# p2_regulator.net
KiCad netlist of a schematic drawn in Altium Designer
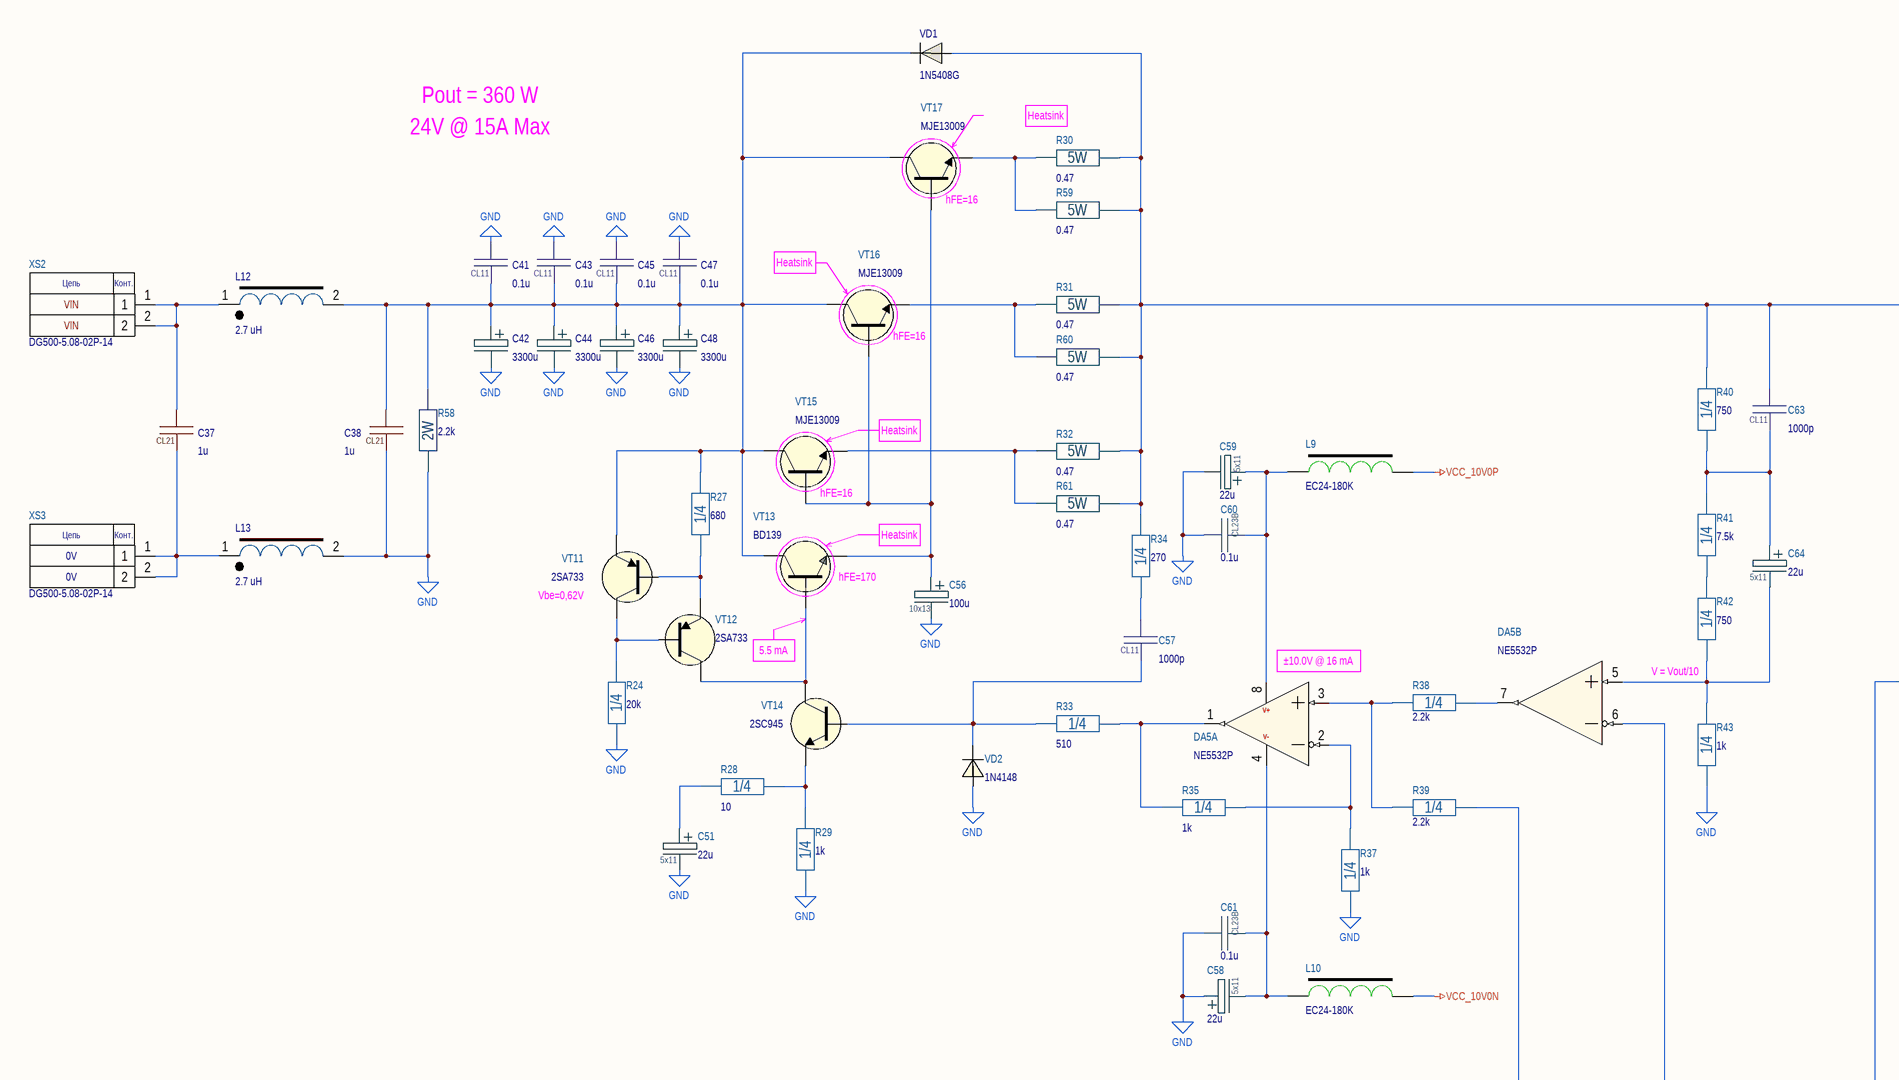
[diagram p0: p2_regulator.SchDoc, top left]
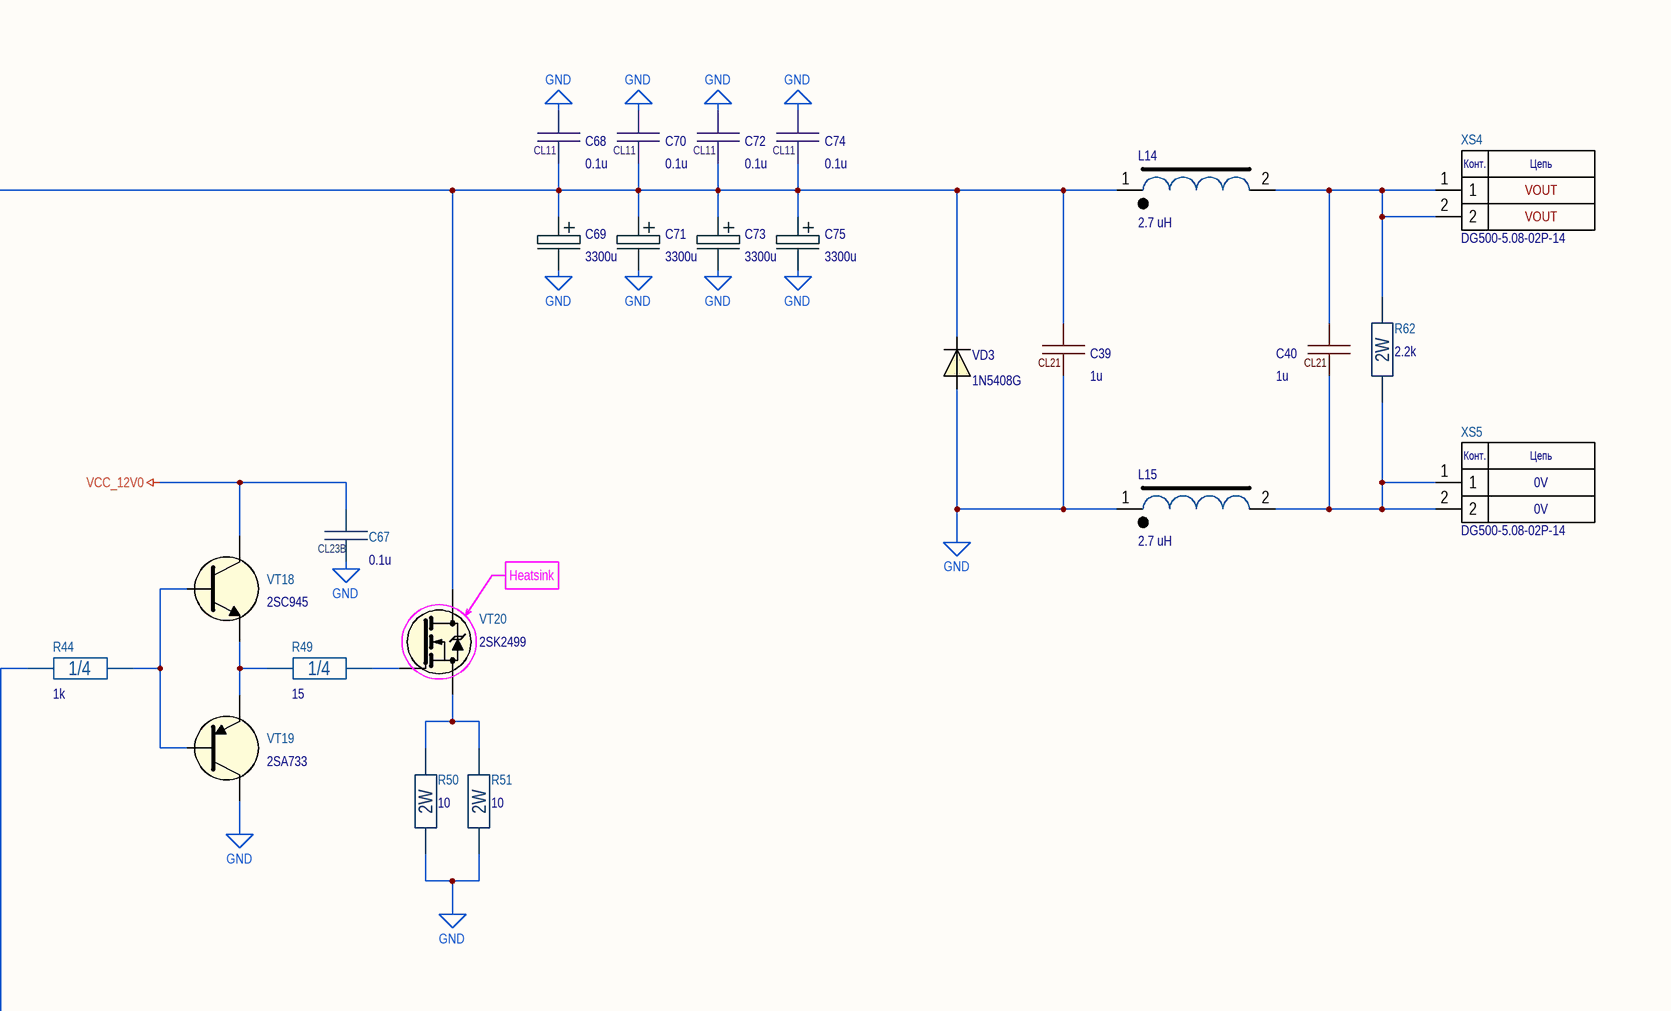
[diagram p1: p2_regulator.SchDoc, top right]
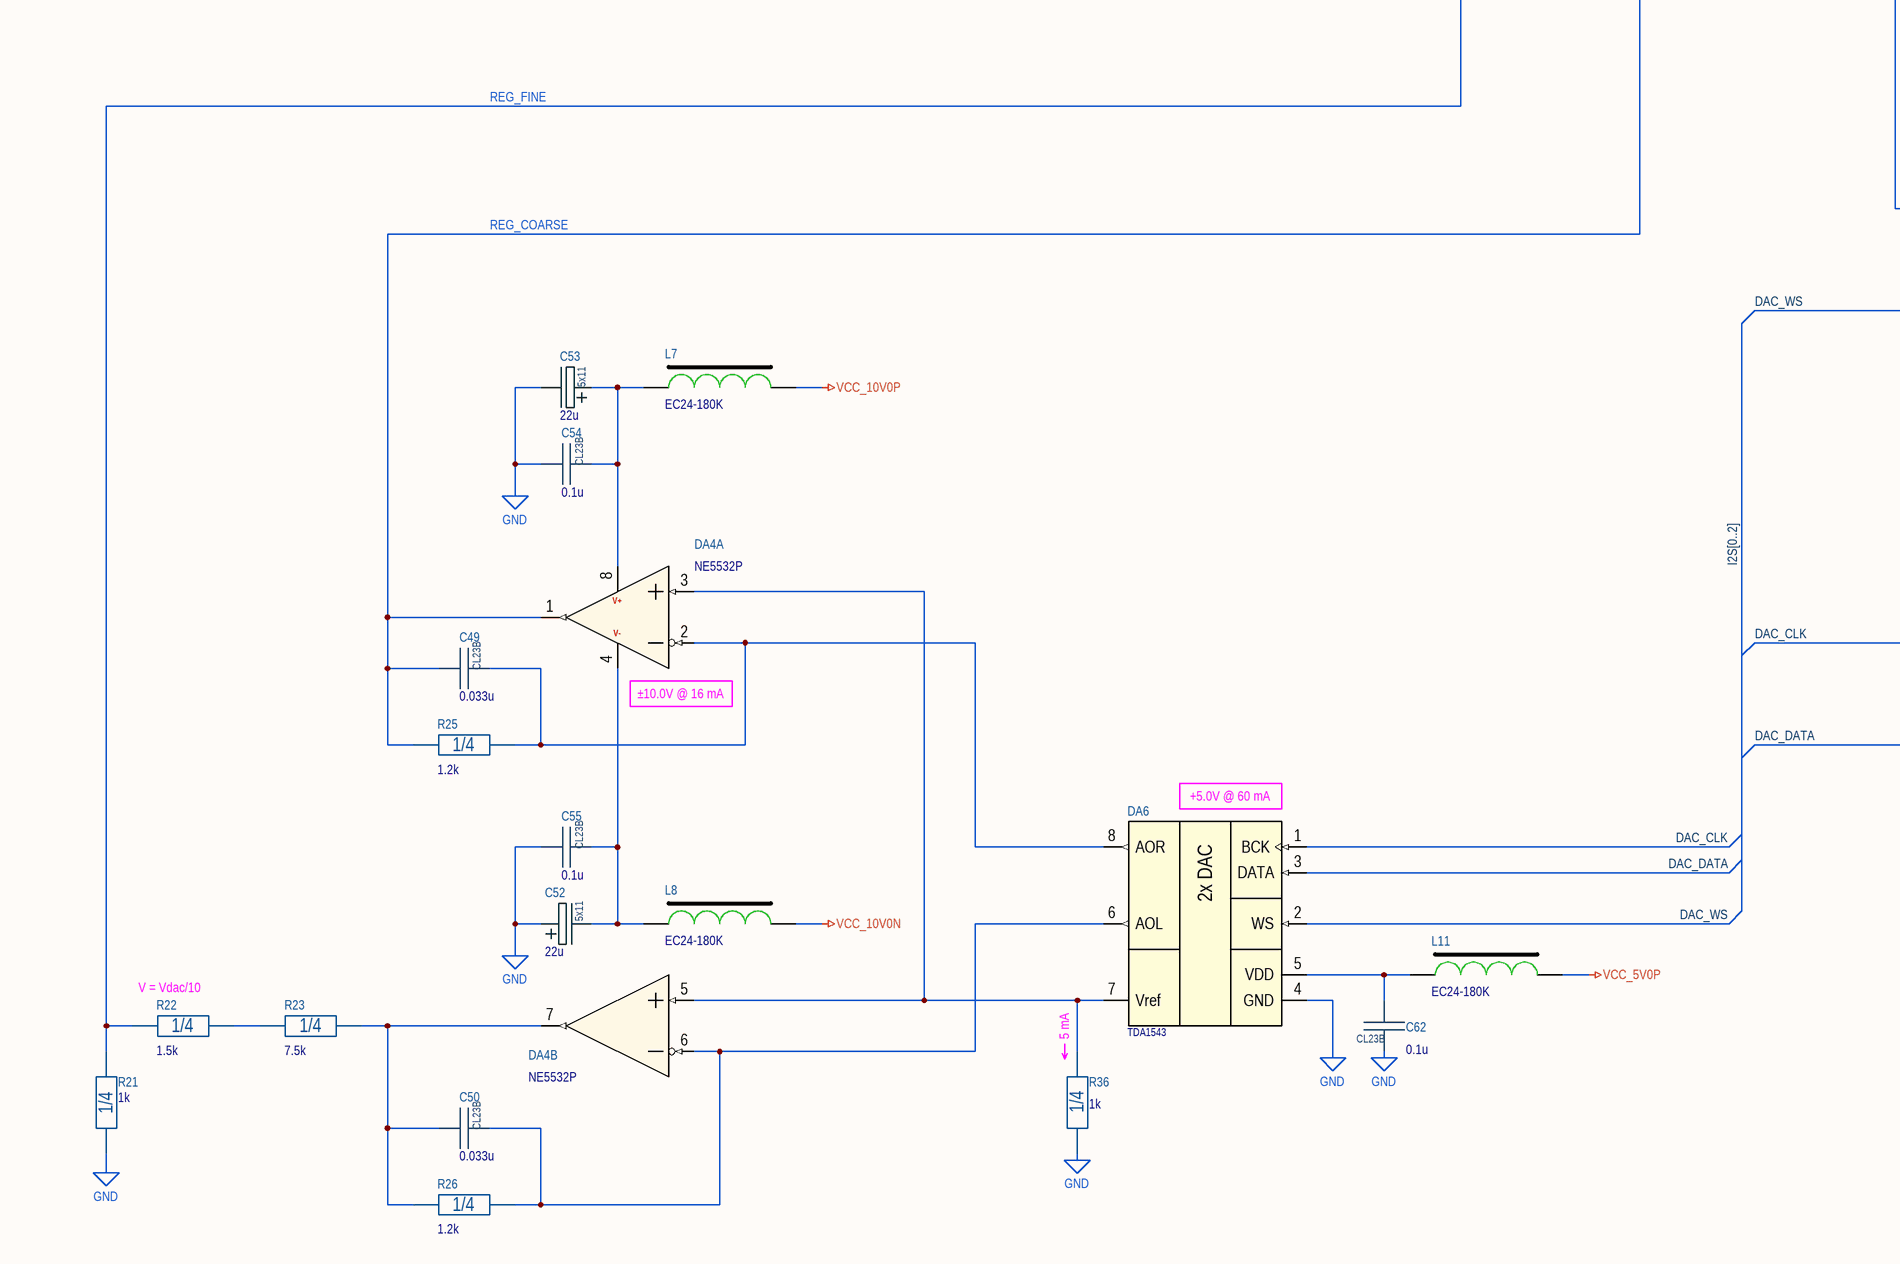
[diagram p2: p2_regulator.SchDoc, bottom left]
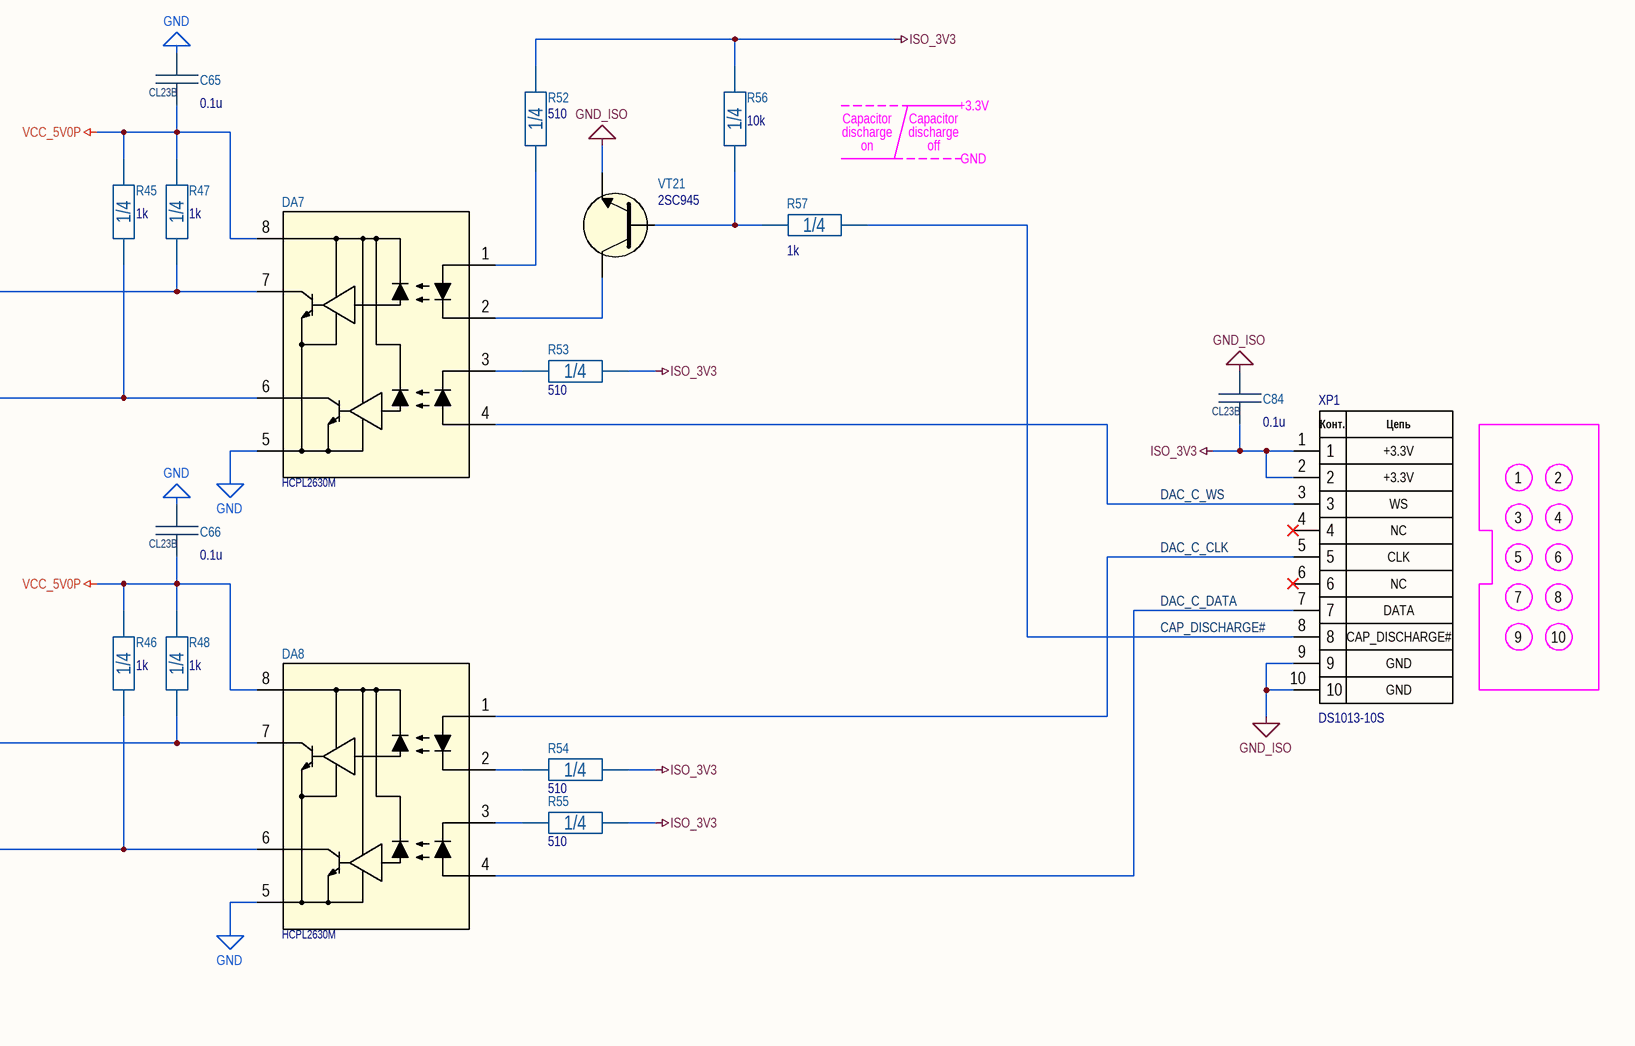
[diagram p3: p2_regulator.SchDoc, bottom right]

(export (version "E")
  (design (tool "Eeschema 10.0.6"))
  (components
    (comp (ref "C37")
      (value "1u")
      (footprint "PcbLib_RC:CL21_29x13.5x6.5_P27.5")
      (description "CL21 Type Metallized Polyester Film Capacitor")
      (fields
        (field (name "TOLERANCE") "± * %")
        (field (name "VOLTAGE") "250V")
        (field (name "PACKAGE") "CL21")
      )
      (libsource (lib "Schlib_RC") (part "CL21"))
    )
    (comp (ref "C38")
      (value "1u")
      (footprint "PcbLib_RC:CL21_29x13.5x6.5_P27.5")
      (description "CL21 Type Metallized Polyester Film Capacitor")
      (fields
        (field (name "TOLERANCE") "± * %")
        (field (name "VOLTAGE") "250V")
        (field (name "PACKAGE") "CL21")
      )
      (libsource (lib "Schlib_RC") (part "CL21"))
    )
    (comp (ref "C39")
      (value "1u")
      (footprint "PcbLib_RC:CL21_29x13.5x6.5_P27.5")
      (description "CL21 Type Metallized Polyester Film Capacitor")
      (fields
        (field (name "TOLERANCE") "± * %")
        (field (name "VOLTAGE") "250V")
        (field (name "PACKAGE") "CL21")
      )
      (libsource (lib "Schlib_RC") (part "CL21"))
    )
    (comp (ref "C40")
      (value "1u")
      (footprint "PcbLib_RC:CL21_29x13.5x6.5_P27.5")
      (description "CL21 Type Metallized Polyester Film Capacitor")
      (fields
        (field (name "TOLERANCE") "± * %")
        (field (name "VOLTAGE") "250V")
        (field (name "PACKAGE") "CL21")
      )
      (libsource (lib "Schlib_RC") (part "CL21"))
    )
    (comp (ref "C41")
      (value "0.1u")
      (footprint "PcbLib_RC:CL11_11.5x7_P7.5")
      (description "CL11 Type Polyester Film Metal Foil Capacitor-inductive")
      (fields
        (field (name "TOLERANCE") "± * %")
        (field (name "VOLTAGE") "100V")
        (field (name "PACKAGE") "CL11")
      )
      (libsource (lib "Schlib_RC") (part "CL11"))
    )
    (comp (ref "C42")
      (value "3300u")
      (footprint "PcbLib_RC:ECAP16X36X75_BLK")
      (description "Aluminium capacitor")
      (fields (field (name "TOLERANCE") "± 20 %") (field (name "VOLTAGE") "50V"))
      (libsource (lib "Schlib_RC") (part "C_ECAP"))
    )
    (comp (ref "C43")
      (value "0.1u")
      (footprint "PcbLib_RC:CL11_11.5x7_P7.5")
      (description "CL11 Type Polyester Film Metal Foil Capacitor-inductive")
      (fields
        (field (name "TOLERANCE") "± * %")
        (field (name "VOLTAGE") "100V")
        (field (name "PACKAGE") "CL11")
      )
      (libsource (lib "Schlib_RC") (part "CL11"))
    )
    (comp (ref "C44")
      (value "3300u")
      (footprint "PcbLib_RC:ECAP16X36X75_BLK")
      (description "Aluminium capacitor")
      (fields (field (name "TOLERANCE") "± 20 %") (field (name "VOLTAGE") "50V"))
      (libsource (lib "Schlib_RC") (part "C_ECAP"))
    )
    (comp (ref "C45")
      (value "0.1u")
      (footprint "PcbLib_RC:CL11_11.5x7_P7.5")
      (description "CL11 Type Polyester Film Metal Foil Capacitor-inductive")
      (fields
        (field (name "TOLERANCE") "± * %")
        (field (name "VOLTAGE") "100V")
        (field (name "PACKAGE") "CL11")
      )
      (libsource (lib "Schlib_RC") (part "CL11"))
    )
    (comp (ref "C46")
      (value "3300u")
      (footprint "PcbLib_RC:ECAP16X36X75_BLK")
      (description "Aluminium capacitor")
      (fields (field (name "TOLERANCE") "± 20 %") (field (name "VOLTAGE") "50V"))
      (libsource (lib "Schlib_RC") (part "C_ECAP"))
    )
    (comp (ref "C47")
      (value "0.1u")
      (footprint "PcbLib_RC:CL11_11.5x7_P7.5")
      (description "CL11 Type Polyester Film Metal Foil Capacitor-inductive")
      (fields
        (field (name "TOLERANCE") "± * %")
        (field (name "VOLTAGE") "100V")
        (field (name "PACKAGE") "CL11")
      )
      (libsource (lib "Schlib_RC") (part "CL11"))
    )
    (comp (ref "C48")
      (value "3300u")
      (footprint "PcbLib_RC:ECAP16X36X75_BLK")
      (description "Aluminium capacitor")
      (fields (field (name "TOLERANCE") "± 20 %") (field (name "VOLTAGE") "50V"))
      (libsource (lib "Schlib_RC") (part "C_ECAP"))
    )
    (comp (ref "C49")
      (value "0.033u")
      (footprint "PcbLib_RC:CL23B_7.2x2.5")
      (description "Box-type metallized polyester film capacitor")
      (fields
        (field (name "TOLERANCE") "± * %")
        (field (name "VOLTAGE") "63V")
        (field (name "PACKAGE") "CL23B")
      )
      (libsource (lib "Schlib_RC") (part "CL23B"))
    )
    (comp (ref "C50")
      (value "0.033u")
      (footprint "PcbLib_RC:CL23B_7.2x2.5")
      (description "Box-type metallized polyester film capacitor")
      (fields
        (field (name "TOLERANCE") "± * %")
        (field (name "VOLTAGE") "63V")
        (field (name "PACKAGE") "CL23B")
      )
      (libsource (lib "Schlib_RC") (part "CL23B"))
    )
    (comp (ref "C51")
      (value "22u")
      (footprint "PcbLib_RC:ECAP5X11X2.0_BRW")
      (description "Aluminium capacitor")
      (fields
        (field (name "TOLERANCE") "± 20 %")
        (field (name "VOLTAGE") "63V")
        (field (name "PACKAGE") "5x11")
      )
      (libsource (lib "Schlib_RC") (part "C_ECAP"))
    )
    (comp (ref "C52")
      (value "22u")
      (footprint "PcbLib_RC:ECAP5X11X2.0_BRW")
      (description "Aluminium capacitor")
      (fields
        (field (name "TOLERANCE") "± 20 %")
        (field (name "VOLTAGE") "63V")
        (field (name "PACKAGE") "5x11")
      )
      (libsource (lib "Schlib_RC") (part "C_ECAP"))
    )
    (comp (ref "C53")
      (value "22u")
      (footprint "PcbLib_RC:ECAP5X11X2.0_BRW")
      (description "Aluminium capacitor")
      (fields
        (field (name "TOLERANCE") "± 20 %")
        (field (name "VOLTAGE") "63V")
        (field (name "PACKAGE") "5x11")
      )
      (libsource (lib "Schlib_RC") (part "C_ECAP"))
    )
    (comp (ref "C54")
      (value "0.1u")
      (footprint "PcbLib_RC:CL23B_7.2x2.5")
      (description "Box-type metallized polyester film capacitor")
      (fields
        (field (name "TOLERANCE") "± * %")
        (field (name "VOLTAGE") "63V")
        (field (name "PACKAGE") "CL23B")
      )
      (libsource (lib "Schlib_RC") (part "CL23B"))
    )
    (comp (ref "C55")
      (value "0.1u")
      (footprint "PcbLib_RC:CL23B_7.2x2.5")
      (description "Box-type metallized polyester film capacitor")
      (fields
        (field (name "TOLERANCE") "± * %")
        (field (name "VOLTAGE") "63V")
        (field (name "PACKAGE") "CL23B")
      )
      (libsource (lib "Schlib_RC") (part "CL23B"))
    )
    (comp (ref "C56")
      (value "100u")
      (footprint "PcbLib_RC:ECAP10X13X5_BRW")
      (description "Aluminium capacitor")
      (fields
        (field (name "TOLERANCE") "± 20 %")
        (field (name "VOLTAGE") "63V")
        (field (name "PACKAGE") "10x13")
      )
      (libsource (lib "Schlib_RC") (part "C_ECAP"))
    )
    (comp (ref "C57")
      (value "1000p")
      (footprint "PcbLib_RC:CL11_6x3.5_P3.5")
      (description "CL11 Type Polyester Film Metal Foil Capacitor-inductive")
      (fields
        (field (name "TOLERANCE") "± 5 %")
        (field (name "VOLTAGE") "100V")
        (field (name "PACKAGE") "CL11")
      )
      (libsource (lib "Schlib_RC") (part "CL11"))
    )
    (comp (ref "C58")
      (value "22u")
      (footprint "PcbLib_RC:ECAP5X11X2.0_BRW")
      (description "Aluminium capacitor")
      (fields
        (field (name "TOLERANCE") "± 20 %")
        (field (name "VOLTAGE") "63V")
        (field (name "PACKAGE") "5x11")
      )
      (libsource (lib "Schlib_RC") (part "C_ECAP"))
    )
    (comp (ref "C59")
      (value "22u")
      (footprint "PcbLib_RC:ECAP5X11X2.0_BRW")
      (description "Aluminium capacitor")
      (fields
        (field (name "TOLERANCE") "± 20 %")
        (field (name "VOLTAGE") "63V")
        (field (name "PACKAGE") "5x11")
      )
      (libsource (lib "Schlib_RC") (part "C_ECAP"))
    )
    (comp (ref "C60")
      (value "0.1u")
      (footprint "PcbLib_RC:CL23B_7.2x2.5")
      (description "Box-type metallized polyester film capacitor")
      (fields
        (field (name "TOLERANCE") "± * %")
        (field (name "VOLTAGE") "63V")
        (field (name "PACKAGE") "CL23B")
      )
      (libsource (lib "Schlib_RC") (part "CL23B"))
    )
    (comp (ref "C61")
      (value "0.1u")
      (footprint "PcbLib_RC:CL23B_7.2x2.5")
      (description "Box-type metallized polyester film capacitor")
      (fields
        (field (name "TOLERANCE") "± * %")
        (field (name "VOLTAGE") "63V")
        (field (name "PACKAGE") "CL23B")
      )
      (libsource (lib "Schlib_RC") (part "CL23B"))
    )
    (comp (ref "C62")
      (value "0.1u")
      (footprint "PcbLib_RC:CL23B_7.2x2.5")
      (description "Box-type metallized polyester film capacitor")
      (fields
        (field (name "TOLERANCE") "± * %")
        (field (name "VOLTAGE") "63V")
        (field (name "PACKAGE") "CL23B")
      )
      (libsource (lib "Schlib_RC") (part "CL23B"))
    )
    (comp (ref "C63")
      (value "1000p")
      (footprint "PcbLib_RC:CL11_6x3.5_P3.5")
      (description "CL11 Type Polyester Film Metal Foil Capacitor-inductive")
      (fields
        (field (name "TOLERANCE") "± 5 %")
        (field (name "VOLTAGE") "100V")
        (field (name "PACKAGE") "CL11")
      )
      (libsource (lib "Schlib_RC") (part "CL11"))
    )
    (comp (ref "C64")
      (value "22u")
      (footprint "PcbLib_RC:ECAP5X11X2.0_BRW")
      (description "Aluminium capacitor")
      (fields
        (field (name "TOLERANCE") "± 20 %")
        (field (name "VOLTAGE") "63V")
        (field (name "PACKAGE") "5x11")
      )
      (libsource (lib "Schlib_RC") (part "C_ECAP"))
    )
    (comp (ref "C65")
      (value "0.1u")
      (footprint "PcbLib_RC:CL23B_7.2x2.5")
      (description "Box-type metallized polyester film capacitor")
      (fields
        (field (name "TOLERANCE") "± * %")
        (field (name "VOLTAGE") "63V")
        (field (name "PACKAGE") "CL23B")
      )
      (libsource (lib "Schlib_RC") (part "CL23B"))
    )
    (comp (ref "C66")
      (value "0.1u")
      (footprint "PcbLib_RC:CL23B_7.2x2.5")
      (description "Box-type metallized polyester film capacitor")
      (fields
        (field (name "TOLERANCE") "± * %")
        (field (name "VOLTAGE") "63V")
        (field (name "PACKAGE") "CL23B")
      )
      (libsource (lib "Schlib_RC") (part "CL23B"))
    )
    (comp (ref "C67")
      (value "0.1u")
      (footprint "PcbLib_RC:CL23B_7.2x2.5")
      (description "Box-type metallized polyester film capacitor")
      (fields
        (field (name "TOLERANCE") "± * %")
        (field (name "VOLTAGE") "63V")
        (field (name "PACKAGE") "CL23B")
      )
      (libsource (lib "Schlib_RC") (part "CL23B"))
    )
    (comp (ref "C68")
      (value "0.1u")
      (footprint "PcbLib_RC:CL11_11.5x7_P7.5")
      (description "CL11 Type Polyester Film Metal Foil Capacitor-inductive")
      (fields
        (field (name "TOLERANCE") "± * %")
        (field (name "VOLTAGE") "100V")
        (field (name "PACKAGE") "CL11")
      )
      (libsource (lib "Schlib_RC") (part "CL11"))
    )
    (comp (ref "C69")
      (value "3300u")
      (footprint "PcbLib_RC:ECAP16X36X75_BLK")
      (description "Aluminium capacitor")
      (fields (field (name "TOLERANCE") "± 20 %") (field (name "VOLTAGE") "50V"))
      (libsource (lib "Schlib_RC") (part "C_ECAP"))
    )
    (comp (ref "C70")
      (value "0.1u")
      (footprint "PcbLib_RC:CL11_11.5x7_P7.5")
      (description "CL11 Type Polyester Film Metal Foil Capacitor-inductive")
      (fields
        (field (name "TOLERANCE") "± * %")
        (field (name "VOLTAGE") "100V")
        (field (name "PACKAGE") "CL11")
      )
      (libsource (lib "Schlib_RC") (part "CL11"))
    )
    (comp (ref "C71")
      (value "3300u")
      (footprint "PcbLib_RC:ECAP16X36X75_BLK")
      (description "Aluminium capacitor")
      (fields (field (name "TOLERANCE") "± 20 %") (field (name "VOLTAGE") "50V"))
      (libsource (lib "Schlib_RC") (part "C_ECAP"))
    )
    (comp (ref "C72")
      (value "0.1u")
      (footprint "PcbLib_RC:CL11_11.5x7_P7.5")
      (description "CL11 Type Polyester Film Metal Foil Capacitor-inductive")
      (fields
        (field (name "TOLERANCE") "± * %")
        (field (name "VOLTAGE") "100V")
        (field (name "PACKAGE") "CL11")
      )
      (libsource (lib "Schlib_RC") (part "CL11"))
    )
    (comp (ref "C73")
      (value "3300u")
      (footprint "PcbLib_RC:ECAP16X36X75_BLK")
      (description "Aluminium capacitor")
      (fields (field (name "TOLERANCE") "± 20 %") (field (name "VOLTAGE") "50V"))
      (libsource (lib "Schlib_RC") (part "C_ECAP"))
    )
    (comp (ref "C74")
      (value "0.1u")
      (footprint "PcbLib_RC:CL11_11.5x7_P7.5")
      (description "CL11 Type Polyester Film Metal Foil Capacitor-inductive")
      (fields
        (field (name "TOLERANCE") "± * %")
        (field (name "VOLTAGE") "100V")
        (field (name "PACKAGE") "CL11")
      )
      (libsource (lib "Schlib_RC") (part "CL11"))
    )
    (comp (ref "C75")
      (value "3300u")
      (footprint "PcbLib_RC:ECAP16X36X75_BLK")
      (description "Aluminium capacitor")
      (fields (field (name "TOLERANCE") "± 20 %") (field (name "VOLTAGE") "50V"))
      (libsource (lib "Schlib_RC") (part "C_ECAP"))
    )
    (comp (ref "C84")
      (value "0.1u")
      (footprint "PcbLib_RC:CL23B_7.2x2.5")
      (description "Box-type metallized polyester film capacitor")
      (fields
        (field (name "TOLERANCE") "± * %")
        (field (name "VOLTAGE") "63V")
        (field (name "PACKAGE") "CL23B")
      )
      (libsource (lib "Schlib_RC") (part "CL23B"))
    )
    (comp (ref "DA4")
      (value "NE5532P")
      (footprint "PcbLib_ICs:DIP-8P-M01_with_SO8")
      (description "DUAL LOW-NOISE OPERATIONAL AMPLIFIERS")
      (fields (field (name "MANUFACTURER") "Texas Instruments"))
      (libsource (lib "Schlib_Texas_Instruments") (part "NE5532P"))
    )
    (comp (ref "DA5")
      (value "NE5532P")
      (footprint "PcbLib_ICs:DIP-8P-M01")
      (description "DUAL LOW-NOISE OPERATIONAL AMPLIFIERS")
      (fields (field (name "MANUFACTURER") "Texas Instruments"))
      (libsource (lib "Schlib_Texas_Instruments") (part "NE5532P"))
    )
    (comp (ref "DA6")
      (value "TDA1543")
      (footprint "PcbLib_ICs:DIP-8P-M01")
      (description "Dual 16-bit DAC, I2S input format")
      (fields (field (name "MANUFACTURER") "Philips"))
      (libsource (lib "Schlib_OtherComponents") (part "TDA1543"))
    )
    (comp (ref "DA7")
      (value "HCPL2630M")
      (footprint "PcbLib_ICs:DIP-8P-M01")
      (description "Dual-Channel High-Speed 10 MBit/s Logic Gate Optocouplers")
      (fields (field (name "MANUFACTURER") "ON Semiconductor"))
      (libsource (lib "Schlib_ONSemiconductor") (part "HCPL2630M"))
    )
    (comp (ref "DA8")
      (value "HCPL2630M")
      (footprint "PcbLib_ICs:DIP-8P-M01")
      (description "Dual-Channel High-Speed 10 MBit/s Logic Gate Optocouplers")
      (fields (field (name "MANUFACTURER") "ON Semiconductor"))
      (libsource (lib "Schlib_ONSemiconductor") (part "HCPL2630M"))
    )
    (comp (ref "L7")
      (value "EC24-180K")
      (footprint "PcbLib_RC:EC24_GREEN")
      (description "Axial leaded coated inductors")
      (fields (field (name "MANUFACTURER") "3L Electronic"))
      (libsource (lib "Schlib_RC") (part "EC24"))
    )
    (comp (ref "L8")
      (value "EC24-180K")
      (footprint "PcbLib_RC:EC24_GREEN")
      (description "Axial leaded coated inductors")
      (fields (field (name "MANUFACTURER") "3L Electronic"))
      (libsource (lib "Schlib_RC") (part "EC24"))
    )
    (comp (ref "L9")
      (value "EC24-180K")
      (footprint "PcbLib_RC:EC24_GREEN")
      (description "Axial leaded coated inductors")
      (fields (field (name "MANUFACTURER") "3L Electronic"))
      (libsource (lib "Schlib_RC") (part "EC24"))
    )
    (comp (ref "L10")
      (value "EC24-180K")
      (footprint "PcbLib_RC:EC24_GREEN")
      (description "Axial leaded coated inductors")
      (fields (field (name "MANUFACTURER") "3L Electronic"))
      (libsource (lib "Schlib_RC") (part "EC24"))
    )
    (comp (ref "L11")
      (value "EC24-180K")
      (footprint "PcbLib_RC:EC24_GREEN")
      (description "Axial leaded coated inductors")
      (fields (field (name "MANUFACTURER") "3L Electronic"))
      (libsource (lib "Schlib_RC") (part "EC24"))
    )
    (comp (ref "L12")
      (value "2.7 uH")
      (footprint "PcbLib_RC:CORE_D20_GB")
      (description "Ferrite Core D20.3/12.7/6.35 mm")
      (libsource (lib "Schlib_OtherComponents") (part "CORE_D20"))
    )
    (comp (ref "L13")
      (value "2.7 uH")
      (footprint "PcbLib_RC:CORE_D20_GB")
      (description "Ferrite Core D20.3/12.7/6.35 mm")
      (libsource (lib "Schlib_OtherComponents") (part "CORE_D20"))
    )
    (comp (ref "L14")
      (value "2.7 uH")
      (footprint "PcbLib_RC:CORE_D20_GB")
      (description "Ferrite Core D20.3/12.7/6.35 mm")
      (libsource (lib "Schlib_OtherComponents") (part "CORE_D20"))
    )
    (comp (ref "L15")
      (value "2.7 uH")
      (footprint "PcbLib_RC:CORE_D20_GB")
      (description "Ferrite Core D20.3/12.7/6.35 mm")
      (libsource (lib "Schlib_OtherComponents") (part "CORE_D20"))
    )
    (comp (ref "R21")
      (value "1k")
      (footprint "PcbLib_RC:CFR-25")
      (description "Resistor 1/4W")
      (fields
        (field (name "TOLERANCE") "± 1 %")
        (field (name "PART NUMBER") "MFR-25FTF52-10K")
        (field (name "PACKAGE") "1/4")
      )
      (libsource (lib "Schlib_RC") (part "CF25"))
    )
    (comp (ref "R22")
      (value "1.5k")
      (footprint "PcbLib_RC:CFR-25")
      (description "Resistor 1/4W")
      (fields
        (field (name "TOLERANCE") "± 1 %")
        (field (name "PART NUMBER") "MFR-25FTF52-1K5")
        (field (name "PACKAGE") "1/4")
      )
      (libsource (lib "Schlib_RC") (part "CF25"))
    )
    (comp (ref "R23")
      (value "7.5k")
      (footprint "PcbLib_RC:CFR-25")
      (description "Resistor 1/4W")
      (fields
        (field (name "TOLERANCE") "± 1 %")
        (field (name "PART NUMBER") "MFR-25FTF52-7K5")
        (field (name "PACKAGE") "1/4")
      )
      (libsource (lib "Schlib_RC") (part "CF25"))
    )
    (comp (ref "R24")
      (value "20k")
      (footprint "PcbLib_RC:CFR-25")
      (description "Resistor 1/4W")
      (fields
        (field (name "TOLERANCE") "± 1 %")
        (field (name "PART NUMBER") "MFR-25FTF52-20K")
        (field (name "PACKAGE") "1/4")
      )
      (libsource (lib "Schlib_RC") (part "CF25"))
    )
    (comp (ref "R25")
      (value "1.2k")
      (footprint "PcbLib_RC:CFR-25")
      (description "Resistor 1/4W")
      (fields
        (field (name "TOLERANCE") "± 1 %")
        (field (name "PART NUMBER") "MFR-25FTF52-1K2")
        (field (name "PACKAGE") "1/4")
      )
      (libsource (lib "Schlib_RC") (part "CF25"))
    )
    (comp (ref "R26")
      (value "1.2k")
      (footprint "PcbLib_RC:CFR-25")
      (description "Resistor 1/4W")
      (fields
        (field (name "TOLERANCE") "± 1 %")
        (field (name "PART NUMBER") "MFR-25FTF52-1K2")
        (field (name "PACKAGE") "1/4")
      )
      (libsource (lib "Schlib_RC") (part "CF25"))
    )
    (comp (ref "R27")
      (value "680")
      (footprint "PcbLib_RC:CFR-25")
      (description "Resistor 1/4W")
      (fields
        (field (name "TOLERANCE") "± 1 %")
        (field (name "PART NUMBER") "MFR-25FTF52-680R")
        (field (name "PACKAGE") "1/4")
      )
      (libsource (lib "Schlib_RC") (part "CF25"))
    )
    (comp (ref "R28")
      (value "10")
      (footprint "PcbLib_RC:CFR-25")
      (description "Resistor 1/4W")
      (fields
        (field (name "TOLERANCE") "± 1 %")
        (field (name "PART NUMBER") "MFR-25FTF52-10R")
        (field (name "PACKAGE") "1/4")
      )
      (libsource (lib "Schlib_RC") (part "CF25"))
    )
    (comp (ref "R29")
      (value "1k")
      (footprint "PcbLib_RC:CFR-25")
      (description "Resistor 1/4W")
      (fields
        (field (name "TOLERANCE") "± 1 %")
        (field (name "PART NUMBER") "MFR-25FTF52-10K")
        (field (name "PACKAGE") "1/4")
      )
      (libsource (lib "Schlib_RC") (part "CF25"))
    )
    (comp (ref "R30")
      (value "0.47")
      (footprint "PcbLib_RC:BPR58")
      (description "Rectangular type metal plate resistors")
      (fields
        (field (name "TOLERANCE") "± 5 %")
        (field (name "PART NUMBER") "BPR58CR47J")
        (field (name "PACKAGE") "5W")
      )
      (libsource (lib "Schlib_RC") (part "BPR58"))
    )
    (comp (ref "R31")
      (value "0.47")
      (footprint "PcbLib_RC:BPR58")
      (description "Rectangular type metal plate resistors")
      (fields
        (field (name "TOLERANCE") "± 5 %")
        (field (name "PART NUMBER") "BPR58CR47J")
        (field (name "PACKAGE") "5W")
      )
      (libsource (lib "Schlib_RC") (part "BPR58"))
    )
    (comp (ref "R32")
      (value "0.47")
      (footprint "PcbLib_RC:BPR58")
      (description "Rectangular type metal plate resistors")
      (fields
        (field (name "TOLERANCE") "± 5 %")
        (field (name "PART NUMBER") "BPR58CR47J")
        (field (name "PACKAGE") "5W")
      )
      (libsource (lib "Schlib_RC") (part "BPR58"))
    )
    (comp (ref "R33")
      (value "510")
      (footprint "PcbLib_RC:CFR-25")
      (description "Resistor 1/4W")
      (fields
        (field (name "TOLERANCE") "± 1 %")
        (field (name "PART NUMBER") "MFR-25FTF52-510R")
        (field (name "PACKAGE") "1/4")
      )
      (libsource (lib "Schlib_RC") (part "CF25"))
    )
    (comp (ref "R34")
      (value "270")
      (footprint "PcbLib_RC:CFR-25")
      (description "Resistor 1/4W")
      (fields
        (field (name "TOLERANCE") "± 1 %")
        (field (name "PART NUMBER") "MFR-25FTF52-270R")
        (field (name "PACKAGE") "1/4")
      )
      (libsource (lib "Schlib_RC") (part "CF25"))
    )
    (comp (ref "R35")
      (value "1k")
      (footprint "PcbLib_RC:CFR-25")
      (description "Resistor 1/4W")
      (fields
        (field (name "TOLERANCE") "± 1 %")
        (field (name "PART NUMBER") "MFR-25FTF52-10K")
        (field (name "PACKAGE") "1/4")
      )
      (libsource (lib "Schlib_RC") (part "CF25"))
    )
    (comp (ref "R36")
      (value "1k")
      (footprint "PcbLib_RC:CFR-25")
      (description "Resistor 1/4W")
      (fields
        (field (name "TOLERANCE") "± 0.1 %")
        (field (name "PART NUMBER") "MFP-25BRD52-1K")
        (field (name "PACKAGE") "1/4")
      )
      (libsource (lib "Schlib_RC") (part "CF25"))
    )
    (comp (ref "R37")
      (value "1k")
      (footprint "PcbLib_RC:CFR-25")
      (description "Resistor 1/4W")
      (fields
        (field (name "TOLERANCE") "± 1 %")
        (field (name "PART NUMBER") "MFR-25FTF52-10K")
        (field (name "PACKAGE") "1/4")
      )
      (libsource (lib "Schlib_RC") (part "CF25"))
    )
    (comp (ref "R38")
      (value "2.2k")
      (footprint "PcbLib_RC:CFR-25")
      (description "Resistor 1/4W")
      (fields
        (field (name "TOLERANCE") "± 1 %")
        (field (name "PART NUMBER") "MFR-25FTF52-2K2")
        (field (name "PACKAGE") "1/4")
      )
      (libsource (lib "Schlib_RC") (part "CF25"))
    )
    (comp (ref "R39")
      (value "2.2k")
      (footprint "PcbLib_RC:CFR-25")
      (description "Resistor 1/4W")
      (fields
        (field (name "TOLERANCE") "± 1 %")
        (field (name "PART NUMBER") "MFR-25FTF52-2K2")
        (field (name "PACKAGE") "1/4")
      )
      (libsource (lib "Schlib_RC") (part "CF25"))
    )
    (comp (ref "R40")
      (value "750")
      (footprint "PcbLib_RC:CFR-25")
      (description "Resistor 1/4W")
      (fields
        (field (name "TOLERANCE") "± 1 %")
        (field (name "PART NUMBER") "MFR-25FTF52-750R")
        (field (name "PACKAGE") "1/4")
      )
      (libsource (lib "Schlib_RC") (part "CF25"))
    )
    (comp (ref "R41")
      (value "7.5k")
      (footprint "PcbLib_RC:CFR-25")
      (description "Resistor 1/4W")
      (fields
        (field (name "TOLERANCE") "± 1 %")
        (field (name "PART NUMBER") "MFR-25FTF52-7K5")
        (field (name "PACKAGE") "1/4")
      )
      (libsource (lib "Schlib_RC") (part "CF25"))
    )
    (comp (ref "R42")
      (value "750")
      (footprint "PcbLib_RC:CFR-25")
      (description "Resistor 1/4W")
      (fields
        (field (name "TOLERANCE") "± 1 %")
        (field (name "PART NUMBER") "MFR-25FTF52-750R")
        (field (name "PACKAGE") "1/4")
      )
      (libsource (lib "Schlib_RC") (part "CF25"))
    )
    (comp (ref "R43")
      (value "1k")
      (footprint "PcbLib_RC:CFR-25")
      (description "Resistor 1/4W")
      (fields
        (field (name "TOLERANCE") "± 1 %")
        (field (name "PART NUMBER") "MFR-25FTF52-1K")
        (field (name "PACKAGE") "1/4")
      )
      (libsource (lib "Schlib_RC") (part "CF25"))
    )
    (comp (ref "R44")
      (value "1k")
      (footprint "PcbLib_RC:CFR-25")
      (description "Resistor 1/4W")
      (fields
        (field (name "TOLERANCE") "± 1 %")
        (field (name "PART NUMBER") "MFR-25FTF52-1K")
        (field (name "PACKAGE") "1/4")
      )
      (libsource (lib "Schlib_RC") (part "CF25"))
    )
    (comp (ref "R45")
      (value "1k")
      (footprint "PcbLib_RC:CFR-25")
      (description "Resistor 1/4W")
      (fields
        (field (name "TOLERANCE") "± 1 %")
        (field (name "PART NUMBER") "MFR-25FTF52-1K")
        (field (name "PACKAGE") "1/4")
      )
      (libsource (lib "Schlib_RC") (part "CF25"))
    )
    (comp (ref "R46")
      (value "1k")
      (footprint "PcbLib_RC:CFR-25")
      (description "Resistor 1/4W")
      (fields
        (field (name "TOLERANCE") "± 1 %")
        (field (name "PART NUMBER") "MFR-25FTF52-1K")
        (field (name "PACKAGE") "1/4")
      )
      (libsource (lib "Schlib_RC") (part "CF25"))
    )
    (comp (ref "R47")
      (value "1k")
      (footprint "PcbLib_RC:CFR-25")
      (description "Resistor 1/4W")
      (fields
        (field (name "TOLERANCE") "± 1 %")
        (field (name "PART NUMBER") "MFR-25FTF52-1K")
        (field (name "PACKAGE") "1/4")
      )
      (libsource (lib "Schlib_RC") (part "CF25"))
    )
    (comp (ref "R48")
      (value "1k")
      (footprint "PcbLib_RC:CFR-25")
      (description "Resistor 1/4W")
      (fields
        (field (name "TOLERANCE") "± 1 %")
        (field (name "PART NUMBER") "MFR-25FTF52-1K")
        (field (name "PACKAGE") "1/4")
      )
      (libsource (lib "Schlib_RC") (part "CF25"))
    )
    (comp (ref "R49")
      (value "15")
      (footprint "PcbLib_RC:CFR-25")
      (description "Resistor 1/4W")
      (fields
        (field (name "TOLERANCE") "± 1 %")
        (field (name "PART NUMBER") "MFR-25FTF52-15R")
        (field (name "PACKAGE") "1/4")
      )
      (libsource (lib "Schlib_RC") (part "CF25"))
    )
    (comp (ref "R50")
      (value "10")
      (footprint "PcbLib_RC:CFR-200")
      (description "Resistor 2W")
      (fields
        (field (name "TOLERANCE") "± 5 %")
        (field (name "PART NUMBER") "KNP200JB-73-10R")
        (field (name "PACKAGE") "2W")
      )
      (libsource (lib "Schlib_RC") (part "CF200"))
    )
    (comp (ref "R51")
      (value "10")
      (footprint "PcbLib_RC:CFR-200")
      (description "Resistor 2W")
      (fields
        (field (name "TOLERANCE") "± 5 %")
        (field (name "PART NUMBER") "KNP200JB-73-10R")
        (field (name "PACKAGE") "2W")
      )
      (libsource (lib "Schlib_RC") (part "CF200"))
    )
    (comp (ref "R52")
      (value "510")
      (footprint "PcbLib_RC:CFR-25")
      (description "Resistor 1/4W")
      (fields
        (field (name "TOLERANCE") "± 1 %")
        (field (name "PART NUMBER") "MFR-25FTF52-510R")
        (field (name "PACKAGE") "1/4")
      )
      (libsource (lib "Schlib_RC") (part "CF25"))
    )
    (comp (ref "R53")
      (value "510")
      (footprint "PcbLib_RC:CFR-25")
      (description "Resistor 1/4W")
      (fields
        (field (name "TOLERANCE") "± 1 %")
        (field (name "PART NUMBER") "MFR-25FTF52-510R")
        (field (name "PACKAGE") "1/4")
      )
      (libsource (lib "Schlib_RC") (part "CF25"))
    )
    (comp (ref "R54")
      (value "510")
      (footprint "PcbLib_RC:CFR-25")
      (description "Resistor 1/4W")
      (fields
        (field (name "TOLERANCE") "± 1 %")
        (field (name "PART NUMBER") "MFR-25FTF52-510R")
        (field (name "PACKAGE") "1/4")
      )
      (libsource (lib "Schlib_RC") (part "CF25"))
    )
    (comp (ref "R55")
      (value "510")
      (footprint "PcbLib_RC:CFR-25")
      (description "Resistor 1/4W")
      (fields
        (field (name "TOLERANCE") "± 1 %")
        (field (name "PART NUMBER") "MFR-25FTF52-510R")
        (field (name "PACKAGE") "1/4")
      )
      (libsource (lib "Schlib_RC") (part "CF25"))
    )
    (comp (ref "R56")
      (value "10k")
      (footprint "PcbLib_RC:CFR-25")
      (description "Resistor 1/4W")
      (fields
        (field (name "TOLERANCE") "± 1 %")
        (field (name "PART NUMBER") "MFR-25FTF52-10K")
        (field (name "PACKAGE") "1/4")
      )
      (libsource (lib "Schlib_RC") (part "CF25"))
    )
    (comp (ref "R57")
      (value "1k")
      (footprint "PcbLib_RC:CFR-25")
      (description "Resistor 1/4W")
      (fields
        (field (name "TOLERANCE") "± 1 %")
        (field (name "PART NUMBER") "MFR-25FTF52-1K")
        (field (name "PACKAGE") "1/4")
      )
      (libsource (lib "Schlib_RC") (part "CF25"))
    )
    (comp (ref "R58")
      (value "2.2k")
      (footprint "PcbLib_RC:CFR-200")
      (description "Resistor 2W")
      (fields
        (field (name "TOLERANCE") "± 5 %")
        (field (name "PART NUMBER") "KNP200JB-73-2K2")
        (field (name "PACKAGE") "2W")
      )
      (libsource (lib "Schlib_RC") (part "CF200"))
    )
    (comp (ref "R59")
      (value "0.47")
      (footprint "PcbLib_RC:BPR58")
      (description "Rectangular type metal plate resistors")
      (fields
        (field (name "TOLERANCE") "± 5 %")
        (field (name "PART NUMBER") "BPR58CR47J")
        (field (name "PACKAGE") "5W")
      )
      (libsource (lib "Schlib_RC") (part "BPR58"))
    )
    (comp (ref "R60")
      (value "0.47")
      (footprint "PcbLib_RC:BPR58")
      (description "Rectangular type metal plate resistors")
      (fields
        (field (name "TOLERANCE") "± 5 %")
        (field (name "PART NUMBER") "BPR58CR47J")
        (field (name "PACKAGE") "5W")
      )
      (libsource (lib "Schlib_RC") (part "BPR58"))
    )
    (comp (ref "R61")
      (value "0.47")
      (footprint "PcbLib_RC:BPR58")
      (description "Rectangular type metal plate resistors")
      (fields
        (field (name "TOLERANCE") "± 5 %")
        (field (name "PART NUMBER") "BPR58CR47J")
        (field (name "PACKAGE") "5W")
      )
      (libsource (lib "Schlib_RC") (part "BPR58"))
    )
    (comp (ref "R62")
      (value "2.2k")
      (footprint "PcbLib_RC:CFR-200")
      (description "Resistor 2W")
      (fields
        (field (name "TOLERANCE") "± 5 %")
        (field (name "PART NUMBER") "KNP200JB-73-2K2")
        (field (name "PACKAGE") "2W")
      )
      (libsource (lib "Schlib_RC") (part "CF200"))
    )
    (comp (ref "VD1")
      (value "1N5408G")
      (footprint "PcbLib_Discrete:DO-201AD")
      (description "3A 1000V Standard Recovery Rectifiers Diode")
      (fields (field (name "MANUFACTURER") "ON Semiconductor"))
      (libsource (lib "Schlib_ONSemiconductor") (part "1N5408G"))
    )
    (comp (ref "VD2")
      (value "1N4148")
      (footprint "PcbLib_Discrete:DO-35 GLASS LIGHT RED")
      (description "High-speed diode")
      (libsource (lib "Schlib_NXP_Semiconductors") (part "1N4148"))
    )
    (comp (ref "VD3")
      (value "1N5408G")
      (footprint "PcbLib_Discrete:DO-201AD")
      (description "3A 1000V Standard Recovery Rectifiers Diode")
      (fields (field (name "MANUFACTURER") "ON Semiconductor"))
      (libsource (lib "Schlib_ONSemiconductor") (part "1N5408G"))
    )
    (comp (ref "VT11")
      (value "2SA733")
      (footprint "PcbLib_ICs:TO-92 (VERTICAL,LINE)")
      (description "General Purpose p-n-p Transistors")
      (fields (field (name "MANUFACTURER") "NEC"))
      (libsource (lib "Schlib_NEC") (part "2SA733"))
    )
    (comp (ref "VT12")
      (value "2SA733")
      (footprint "PcbLib_ICs:TO-92 (VERTICAL,LINE)")
      (description "General Purpose p-n-p Transistors")
      (fields (field (name "MANUFACTURER") "NEC"))
      (libsource (lib "Schlib_NEC") (part "2SA733"))
    )
    (comp (ref "VT13")
      (value "BD139")
      (footprint "PcbLib_ICs:TO-126 (VERTICAL)")
      (description "General Purpose n-p-n Transistors")
      (fields (field (name "MANUFACTURER") "STMicroelectronics"))
      (libsource (lib "Schlib_STMicroelectronics") (part "BD139"))
    )
    (comp (ref "VT14")
      (value "2SC945")
      (footprint "PcbLib_ICs:TO-92 (VERTICAL,LINE)")
      (description "General Purpose n-p-n Transistors")
      (fields (field (name "MANUFACTURER") "NEC"))
      (libsource (lib "Schlib_NEC") (part "2SC945"))
    )
    (comp (ref "VT15")
      (value "MJE13009")
      (footprint "PcbLib_ICs:TO-220_with_TO-247 (VERTICAL)SLOT")
      (description "General Purpose n-p-n Transistors 400V, 12A, 100W")
      (fields (field (name "MANUFACTURER") "Inchange Semiconductor"))
      (libsource (lib "Schlib_Inchange_Semiconductor") (part "MJE13009"))
    )
    (comp (ref "VT16")
      (value "MJE13009")
      (footprint "PcbLib_ICs:TO-220_with_TO-247 (VERTICAL)SLOT")
      (description "General Purpose n-p-n Transistors 400V, 12A, 100W")
      (fields (field (name "MANUFACTURER") "Inchange Semiconductor"))
      (libsource (lib "Schlib_Inchange_Semiconductor") (part "MJE13009"))
    )
    (comp (ref "VT17")
      (value "MJE13009")
      (footprint "PcbLib_ICs:TO-220_with_TO-247 (VERTICAL)SLOT")
      (description "General Purpose n-p-n Transistors 400V, 12A, 100W")
      (fields (field (name "MANUFACTURER") "Inchange Semiconductor"))
      (libsource (lib "Schlib_Inchange_Semiconductor") (part "MJE13009"))
    )
    (comp (ref "VT18")
      (value "2SC945")
      (footprint "PcbLib_ICs:TO-92 (VERTICAL,LINE)")
      (description "General Purpose n-p-n Transistors")
      (fields (field (name "MANUFACTURER") "NEC"))
      (libsource (lib "Schlib_NEC") (part "2SC945"))
    )
    (comp (ref "VT19")
      (value "2SA733")
      (footprint "PcbLib_ICs:TO-92 (VERTICAL,LINE)")
      (description "General Purpose p-n-p Transistors")
      (fields (field (name "MANUFACTURER") "NEC"))
      (libsource (lib "Schlib_NEC") (part "2SA733"))
    )
    (comp (ref "VT20")
      (value "2SK2499")
      (footprint "PcbLib_ICs:TO-220AB-3")
      (description "N-Channel MOSFET, 60V, 50A")
      (fields (field (name "MANUFACTURER") "NEC"))
      (libsource (lib "Schlib_NEC") (part "2SK2499"))
    )
    (comp (ref "VT21")
      (value "2SC945")
      (footprint "PcbLib_ICs:TO-92 (VERTICAL,LINE)")
      (description "General Purpose n-p-n Transistors")
      (fields (field (name "MANUFACTURER") "NEC"))
      (libsource (lib "Schlib_NEC") (part "2SC945"))
    )
    (comp (ref "XP1")
      (value "DS1013-10S")
      (footprint "PcbLib_Pin_Headers_part2:BH-10")
      (description "10-pin 2.54 mm Box header elevator type")
      (fields (field (name "MANUFACTURER") "Connfly"))
      (libsource (lib "Schlib_Connfly") (part "BH-10"))
    )
    (comp (ref "XS2")
      (value "DG500-5.08-02P-14")
      (footprint "PcbLib_Connectors:DG500-5.08-02P")
      (description "2-way screw terminal, pitch 200mils (5.08mm)")
      (fields (field (name "MANUFACTURER") "DEGSON"))
      (libsource (lib "Schlib_OtherComponents") (part "DG500-5.08-02P-14"))
    )
    (comp (ref "XS3")
      (value "DG500-5.08-02P-14")
      (footprint "PcbLib_Connectors:DG500-5.08-02P")
      (description "2-way screw terminal, pitch 200mils (5.08mm)")
      (fields (field (name "MANUFACTURER") "DEGSON"))
      (libsource (lib "Schlib_OtherComponents") (part "DG500-5.08-02P-14"))
    )
    (comp (ref "XS4")
      (value "DG500-5.08-02P-14")
      (footprint "PcbLib_Connectors:DG500-5.08-02P")
      (description "2-way screw terminal, pitch 200mils (5.08mm)")
      (fields (field (name "MANUFACTURER") "DEGSON"))
      (libsource (lib "Schlib_OtherComponents") (part "DG500-5.08-02P-14"))
    )
    (comp (ref "XS5")
      (value "DG500-5.08-02P-14")
      (footprint "PcbLib_Connectors:DG500-5.08-02P")
      (description "2-way screw terminal, pitch 200mils (5.08mm)")
      (fields (field (name "MANUFACTURER") "DEGSON"))
      (libsource (lib "Schlib_OtherComponents") (part "DG500-5.08-02P-14"))
    )
  )
  (nets
    (net (code "4") (name "/CAP_DISCHARGE#") (class "Default")
      (node (ref "R57") (pin "2") (pinfunction "2_2") (pintype "passive"))
      (node (ref "XP1") (pin "8") (pinfunction "8_8") (pintype "passive"))
    )
    (net (code "5") (name "/DAC_CLK") (class "Default")
      (node (ref "DA6") (pin "1") (pinfunction "BCK_1") (pintype "input"))
      (node (ref "DA8") (pin "7") (pinfunction "V01_7") (pintype "passive"))
      (node (ref "R48") (pin "2") (pinfunction "2_2") (pintype "passive"))
    )
    (net (code "6") (name "/DAC_C_CLK") (class "Default")
      (node (ref "DA8") (pin "1") (pinfunction "ANODE1_1") (pintype "passive"))
      (node (ref "XP1") (pin "5") (pinfunction "5_5") (pintype "passive"))
    )
    (net (code "7") (name "/DAC_C_DATA") (class "Default")
      (node (ref "DA8") (pin "4") (pinfunction "ANODE2_4") (pintype "passive"))
      (node (ref "XP1") (pin "7") (pinfunction "7_7") (pintype "passive"))
    )
    (net (code "8") (name "/DAC_C_WS") (class "Default")
      (node (ref "DA7") (pin "4") (pinfunction "ANODE2_4") (pintype "passive"))
      (node (ref "XP1") (pin "3") (pinfunction "3_3") (pintype "passive"))
    )
    (net (code "9") (name "/DAC_DATA") (class "Default")
      (node (ref "DA6") (pin "3") (pinfunction "DATA_3") (pintype "input"))
      (node (ref "DA8") (pin "6") (pinfunction "V02_6") (pintype "passive"))
      (node (ref "R46") (pin "2") (pinfunction "2_2") (pintype "passive"))
    )
    (net (code "10") (name "/DAC_WS") (class "Default")
      (node (ref "DA6") (pin "2") (pinfunction "WS_2") (pintype "input"))
      (node (ref "DA7") (pin "6") (pinfunction "V02_6") (pintype "passive"))
      (node (ref "R45") (pin "2") (pinfunction "2_2") (pintype "passive"))
    )
    (net (code "12") (name "/REG_COARSE") (class "Default")
      (node (ref "C49") (pin "2") (pinfunction "2_2") (pintype "passive"))
      (node (ref "DA4") (pin "1") (pinfunction "1OUT_1") (pintype "output"))
      (node (ref "DA5") (pin "6") (pinfunction "2IN-_6") (pintype "input"))
      (node (ref "R25") (pin "1") (pinfunction "1_1") (pintype "passive"))
    )
    (net (code "13") (name "/REG_FINE") (class "Default")
      (node (ref "R21") (pin "2") (pinfunction "2_2") (pintype "passive"))
      (node (ref "R22") (pin "1") (pinfunction "1_1") (pintype "passive"))
      (node (ref "R39") (pin "2") (pinfunction "2_2") (pintype "passive"))
    )
    (net (code "14") (name "GND") (class "Default")
      (node (ref "C38") (pin "1") (pinfunction "1_1") (pintype "passive"))
      (node (ref "C39") (pin "1") (pinfunction "1_1") (pintype "passive"))
      (node (ref "C41") (pin "2") (pinfunction "2_2") (pintype "passive"))
      (node (ref "C42") (pin "2") (pinfunction "2_2") (pintype "passive"))
      (node (ref "C43") (pin "2") (pinfunction "2_2") (pintype "passive"))
      (node (ref "C44") (pin "2") (pinfunction "2_2") (pintype "passive"))
      (node (ref "C45") (pin "2") (pinfunction "2_2") (pintype "passive"))
      (node (ref "C46") (pin "2") (pinfunction "2_2") (pintype "passive"))
      (node (ref "C47") (pin "2") (pinfunction "2_2") (pintype "passive"))
      (node (ref "C48") (pin "2") (pinfunction "2_2") (pintype "passive"))
      (node (ref "C51") (pin "2") (pinfunction "2_2") (pintype "passive"))
      (node (ref "C52") (pin "1") (pinfunction "1_1") (pintype "passive"))
      (node (ref "C53") (pin "2") (pinfunction "2_2") (pintype "passive"))
      (node (ref "C54") (pin "2") (pinfunction "2_2") (pintype "passive"))
      (node (ref "C55") (pin "2") (pinfunction "2_2") (pintype "passive"))
      (node (ref "C56") (pin "2") (pinfunction "2_2") (pintype "passive"))
      (node (ref "C58") (pin "1") (pinfunction "1_1") (pintype "passive"))
      (node (ref "C59") (pin "2") (pinfunction "2_2") (pintype "passive"))
      (node (ref "C60") (pin "2") (pinfunction "2_2") (pintype "passive"))
      (node (ref "C61") (pin "2") (pinfunction "2_2") (pintype "passive"))
      (node (ref "C62") (pin "2") (pinfunction "2_2") (pintype "passive"))
      (node (ref "C65") (pin "1") (pinfunction "1_1") (pintype "passive"))
      (node (ref "C66") (pin "1") (pinfunction "1_1") (pintype "passive"))
      (node (ref "C67") (pin "2") (pinfunction "2_2") (pintype "passive"))
      (node (ref "C68") (pin "2") (pinfunction "2_2") (pintype "passive"))
      (node (ref "C69") (pin "2") (pinfunction "2_2") (pintype "passive"))
      (node (ref "C70") (pin "2") (pinfunction "2_2") (pintype "passive"))
      (node (ref "C71") (pin "2") (pinfunction "2_2") (pintype "passive"))
      (node (ref "C72") (pin "2") (pinfunction "2_2") (pintype "passive"))
      (node (ref "C73") (pin "2") (pinfunction "2_2") (pintype "passive"))
      (node (ref "C74") (pin "2") (pinfunction "2_2") (pintype "passive"))
      (node (ref "C75") (pin "2") (pinfunction "2_2") (pintype "passive"))
      (node (ref "DA6") (pin "4") (pinfunction "GND_4") (pintype "power_in"))
      (node (ref "DA7") (pin "5") (pinfunction "GND_5") (pintype "passive"))
      (node (ref "DA8") (pin "5") (pinfunction "GND_5") (pintype "passive"))
      (node (ref "L13") (pin "2") (pinfunction "2_2") (pintype "passive"))
      (node (ref "L15") (pin "1") (pinfunction "1_1") (pintype "passive"))
      (node (ref "R21") (pin "1") (pinfunction "1_1") (pintype "passive"))
      (node (ref "R24") (pin "2") (pinfunction "2_2") (pintype "passive"))
      (node (ref "R29") (pin "2") (pinfunction "2_2") (pintype "passive"))
      (node (ref "R36") (pin "1") (pinfunction "1_1") (pintype "passive"))
      (node (ref "R37") (pin "2") (pinfunction "2_2") (pintype "passive"))
      (node (ref "R43") (pin "2") (pinfunction "2_2") (pintype "passive"))
      (node (ref "R50") (pin "1") (pinfunction "1_1") (pintype "passive"))
      (node (ref "R51") (pin "1") (pinfunction "1_1") (pintype "passive"))
      (node (ref "R58") (pin "1") (pinfunction "1_1") (pintype "passive"))
      (node (ref "VD2") (pin "2") (pinfunction "2_2") (pintype "passive"))
      (node (ref "VD3") (pin "2") (pinfunction "A_2") (pintype "passive"))
      (node (ref "VT19") (pin "2") (pinfunction "C_2") (pintype "passive"))
    )
    (net (code "15") (name "GND_ISO") (class "Default")
      (node (ref "C84") (pin "1") (pinfunction "1_1") (pintype "passive"))
      (node (ref "VT21") (pin "3") (pinfunction "E_3") (pintype "passive"))
      (node (ref "XP1") (pin "10") (pinfunction "10_10") (pintype "passive"))
      (node (ref "XP1") (pin "9") (pinfunction "9_9") (pintype "passive"))
    )
    (net (code "16") (name "ISO_3V3") (class "Default")
      (node (ref "C84") (pin "2") (pinfunction "2_2") (pintype "passive"))
      (node (ref "R52") (pin "2") (pinfunction "2_2") (pintype "passive"))
      (node (ref "R53") (pin "1") (pinfunction "1_1") (pintype "passive"))
      (node (ref "R54") (pin "1") (pinfunction "1_1") (pintype "passive"))
      (node (ref "R55") (pin "1") (pinfunction "1_1") (pintype "passive"))
      (node (ref "R56") (pin "1") (pinfunction "1_1") (pintype "passive"))
      (node (ref "XP1") (pin "1") (pinfunction "1_1") (pintype "passive"))
      (node (ref "XP1") (pin "2") (pinfunction "2_2") (pintype "passive"))
    )
    (net (code "17") (name "Net-(C37-Pad1)") (class "Default")
      (node (ref "C37") (pin "1") (pinfunction "1_1") (pintype "passive"))
      (node (ref "L13") (pin "1") (pinfunction "1_1") (pintype "passive"))
      (node (ref "XS3") (pin "1") (pinfunction "1_1") (pintype "passive"))
      (node (ref "XS3") (pin "2") (pinfunction "2_2") (pintype "passive"))
    )
    (net (code "18") (name "Net-(C37-Pad2)") (class "Default")
      (node (ref "C37") (pin "2") (pinfunction "2_2") (pintype "passive"))
      (node (ref "L12") (pin "1") (pinfunction "1_1") (pintype "passive"))
      (node (ref "XS2") (pin "1") (pinfunction "1_1") (pintype "passive"))
      (node (ref "XS2") (pin "2") (pinfunction "2_2") (pintype "passive"))
    )
    (net (code "19") (name "Net-(C40-Pad1)") (class "Default")
      (node (ref "C40") (pin "1") (pinfunction "1_1") (pintype "passive"))
      (node (ref "L15") (pin "2") (pinfunction "2_2") (pintype "passive"))
      (node (ref "R62") (pin "1") (pinfunction "1_1") (pintype "passive"))
      (node (ref "XS5") (pin "1") (pinfunction "1_1") (pintype "passive"))
      (node (ref "XS5") (pin "2") (pinfunction "2_2") (pintype "passive"))
    )
    (net (code "20") (name "Net-(C40-Pad2)") (class "Default")
      (node (ref "C40") (pin "2") (pinfunction "2_2") (pintype "passive"))
      (node (ref "L14") (pin "2") (pinfunction "2_2") (pintype "passive"))
      (node (ref "R62") (pin "2") (pinfunction "2_2") (pintype "passive"))
      (node (ref "XS4") (pin "1") (pinfunction "1_1") (pintype "passive"))
      (node (ref "XS4") (pin "2") (pinfunction "2_2") (pintype "passive"))
    )
    (net (code "21") (name "Net-(C51-Pad1)") (class "Default")
      (node (ref "C51") (pin "1") (pinfunction "1_1") (pintype "passive"))
      (node (ref "R28") (pin "2") (pinfunction "2_2") (pintype "passive"))
    )
    (net (code "22") (name "Net-(C57-Pad2)") (class "Default")
      (node (ref "C57") (pin "2") (pinfunction "2_2") (pintype "passive"))
      (node (ref "R34") (pin "2") (pinfunction "2_2") (pintype "passive"))
    )
    (net (code "23") (name "Net-(C63-Pad1)") (class "Default")
      (node (ref "C63") (pin "1") (pinfunction "1_1") (pintype "passive"))
      (node (ref "C64") (pin "1") (pinfunction "1_1") (pintype "passive"))
      (node (ref "R40") (pin "2") (pinfunction "2_2") (pintype "passive"))
      (node (ref "R41") (pin "1") (pinfunction "1_1") (pintype "passive"))
    )
    (net (code "24") (name "Net-(DA4A-1IN+)") (class "Default")
      (node (ref "DA4") (pin "3") (pinfunction "1IN+_3") (pintype "input"))
      (node (ref "DA4") (pin "5") (pinfunction "2IN+_5") (pintype "input"))
      (node (ref "DA6") (pin "7") (pinfunction "Vref_7") (pintype "passive"))
      (node (ref "R36") (pin "2") (pinfunction "2_2") (pintype "passive"))
    )
    (net (code "25") (name "Net-(DA4A-1IN-)") (class "Default")
      (node (ref "C49") (pin "1") (pinfunction "1_1") (pintype "passive"))
      (node (ref "DA4") (pin "2") (pinfunction "1IN-_2") (pintype "input"))
      (node (ref "DA6") (pin "8") (pinfunction "AOR_8") (pintype "output"))
      (node (ref "R25") (pin "2") (pinfunction "2_2") (pintype "passive"))
    )
    (net (code "26") (name "Net-(DA4A-GND)") (class "Default")
      (node (ref "C52") (pin "2") (pinfunction "2_2") (pintype "passive"))
      (node (ref "C55") (pin "1") (pinfunction "1_1") (pintype "passive"))
      (node (ref "DA4") (pin "4") (pinfunction "GND_4") (pintype "power_in"))
      (node (ref "L8") (pin "1") (pinfunction "1_1") (pintype "passive"))
    )
    (net (code "27") (name "Net-(DA4A-VCC)") (class "Default")
      (node (ref "C53") (pin "1") (pinfunction "1_1") (pintype "passive"))
      (node (ref "C54") (pin "1") (pinfunction "1_1") (pintype "passive"))
      (node (ref "DA4") (pin "8") (pinfunction "VCC_8") (pintype "power_in"))
      (node (ref "L7") (pin "1") (pinfunction "1_1") (pintype "passive"))
    )
    (net (code "28") (name "Net-(DA4B-2IN-)") (class "Default")
      (node (ref "C50") (pin "1") (pinfunction "1_1") (pintype "passive"))
      (node (ref "DA4") (pin "6") (pinfunction "2IN-_6") (pintype "input"))
      (node (ref "DA6") (pin "6") (pinfunction "AOL_6") (pintype "output"))
      (node (ref "R26") (pin "2") (pinfunction "2_2") (pintype "passive"))
    )
    (net (code "29") (name "Net-(DA4B-2OUT)") (class "Default")
      (node (ref "C50") (pin "2") (pinfunction "2_2") (pintype "passive"))
      (node (ref "DA4") (pin "7") (pinfunction "2OUT_7") (pintype "output"))
      (node (ref "R23") (pin "2") (pinfunction "2_2") (pintype "passive"))
      (node (ref "R26") (pin "1") (pinfunction "1_1") (pintype "passive"))
    )
    (net (code "30") (name "Net-(DA5A-1IN+)") (class "Default")
      (node (ref "DA5") (pin "3") (pinfunction "1IN+_3") (pintype "input"))
      (node (ref "R38") (pin "1") (pinfunction "1_1") (pintype "passive"))
      (node (ref "R39") (pin "1") (pinfunction "1_1") (pintype "passive"))
    )
    (net (code "31") (name "Net-(DA5A-1IN-)") (class "Default")
      (node (ref "DA5") (pin "2") (pinfunction "1IN-_2") (pintype "input"))
      (node (ref "R35") (pin "2") (pinfunction "2_2") (pintype "passive"))
      (node (ref "R37") (pin "1") (pinfunction "1_1") (pintype "passive"))
    )
    (net (code "32") (name "Net-(DA5A-1OUT)") (class "Default")
      (node (ref "DA5") (pin "1") (pinfunction "1OUT_1") (pintype "output"))
      (node (ref "R33") (pin "2") (pinfunction "2_2") (pintype "passive"))
      (node (ref "R35") (pin "1") (pinfunction "1_1") (pintype "passive"))
    )
    (net (code "33") (name "Net-(DA5A-GND)") (class "Default")
      (node (ref "C58") (pin "2") (pinfunction "2_2") (pintype "passive"))
      (node (ref "C61") (pin "1") (pinfunction "1_1") (pintype "passive"))
      (node (ref "DA5") (pin "4") (pinfunction "GND_4") (pintype "power_in"))
      (node (ref "L10") (pin "1") (pinfunction "1_1") (pintype "passive"))
    )
    (net (code "34") (name "Net-(DA5A-VCC)") (class "Default")
      (node (ref "C59") (pin "1") (pinfunction "1_1") (pintype "passive"))
      (node (ref "C60") (pin "1") (pinfunction "1_1") (pintype "passive"))
      (node (ref "DA5") (pin "8") (pinfunction "VCC_8") (pintype "power_in"))
      (node (ref "L9") (pin "1") (pinfunction "1_1") (pintype "passive"))
    )
    (net (code "35") (name "Net-(DA5B-2IN+)") (class "Default")
      (node (ref "C64") (pin "2") (pinfunction "2_2") (pintype "passive"))
      (node (ref "DA5") (pin "5") (pinfunction "2IN+_5") (pintype "input"))
      (node (ref "R42") (pin "2") (pinfunction "2_2") (pintype "passive"))
      (node (ref "R43") (pin "1") (pinfunction "1_1") (pintype "passive"))
    )
    (net (code "36") (name "Net-(DA5B-2OUT)") (class "Default")
      (node (ref "DA5") (pin "7") (pinfunction "2OUT_7") (pintype "output"))
      (node (ref "R38") (pin "2") (pinfunction "2_2") (pintype "passive"))
    )
    (net (code "37") (name "Net-(DA6-VDD)") (class "Default")
      (node (ref "C62") (pin "1") (pinfunction "1_1") (pintype "passive"))
      (node (ref "DA6") (pin "5") (pinfunction "VDD_5") (pintype "power_in"))
      (node (ref "L11") (pin "1") (pinfunction "1_1") (pintype "passive"))
    )
    (net (code "38") (name "Net-(DA7-ANODE1)") (class "Default")
      (node (ref "DA7") (pin "1") (pinfunction "ANODE1_1") (pintype "passive"))
      (node (ref "R52") (pin "1") (pinfunction "1_1") (pintype "passive"))
    )
    (net (code "39") (name "Net-(DA7-CATHODE1)") (class "Default")
      (node (ref "DA7") (pin "2") (pinfunction "CATHODE1_2") (pintype "power_in"))
      (node (ref "VT21") (pin "2") (pinfunction "C_2") (pintype "passive"))
    )
    (net (code "40") (name "Net-(DA7-CATHODE2)") (class "Default")
      (node (ref "DA7") (pin "3") (pinfunction "CATHODE2_3") (pintype "power_in"))
      (node (ref "R53") (pin "2") (pinfunction "2_2") (pintype "passive"))
    )
    (net (code "41") (name "Net-(DA7-V01)") (class "Default")
      (node (ref "DA7") (pin "7") (pinfunction "V01_7") (pintype "passive"))
      (node (ref "R44") (pin "1") (pinfunction "1_1") (pintype "passive"))
      (node (ref "R47") (pin "2") (pinfunction "2_2") (pintype "passive"))
    )
    (net (code "42") (name "Net-(DA8-CATHODE1)") (class "Default")
      (node (ref "DA8") (pin "2") (pinfunction "CATHODE1_2") (pintype "power_in"))
      (node (ref "R54") (pin "2") (pinfunction "2_2") (pintype "passive"))
    )
    (net (code "43") (name "Net-(DA8-CATHODE2)") (class "Default")
      (node (ref "DA8") (pin "3") (pinfunction "CATHODE2_3") (pintype "power_in"))
      (node (ref "R55") (pin "2") (pinfunction "2_2") (pintype "passive"))
    )
    (net (code "44") (name "Net-(R22-Pad2)") (class "Default")
      (node (ref "R22") (pin "2") (pinfunction "2_2") (pintype "passive"))
      (node (ref "R23") (pin "1") (pinfunction "1_1") (pintype "passive"))
    )
    (net (code "45") (name "Net-(R41-Pad2)") (class "Default")
      (node (ref "R41") (pin "2") (pinfunction "2_2") (pintype "passive"))
      (node (ref "R42") (pin "1") (pinfunction "1_1") (pintype "passive"))
    )
    (net (code "46") (name "Net-(VD1-A)") (class "Default")
      (node (ref "C39") (pin "2") (pinfunction "2_2") (pintype "passive"))
      (node (ref "C63") (pin "2") (pinfunction "2_2") (pintype "passive"))
      (node (ref "C68") (pin "1") (pinfunction "1_1") (pintype "passive"))
      (node (ref "C69") (pin "1") (pinfunction "1_1") (pintype "passive"))
      (node (ref "C70") (pin "1") (pinfunction "1_1") (pintype "passive"))
      (node (ref "C71") (pin "1") (pinfunction "1_1") (pintype "passive"))
      (node (ref "C72") (pin "1") (pinfunction "1_1") (pintype "passive"))
      (node (ref "C73") (pin "1") (pinfunction "1_1") (pintype "passive"))
      (node (ref "C74") (pin "1") (pinfunction "1_1") (pintype "passive"))
      (node (ref "C75") (pin "1") (pinfunction "1_1") (pintype "passive"))
      (node (ref "L14") (pin "1") (pinfunction "1_1") (pintype "passive"))
      (node (ref "R30") (pin "2") (pinfunction "2_2") (pintype "passive"))
      (node (ref "R31") (pin "2") (pinfunction "2_2") (pintype "passive"))
      (node (ref "R32") (pin "2") (pinfunction "2_2") (pintype "passive"))
      (node (ref "R34") (pin "1") (pinfunction "1_1") (pintype "passive"))
      (node (ref "R40") (pin "1") (pinfunction "1_1") (pintype "passive"))
      (node (ref "R59") (pin "2") (pinfunction "2_2") (pintype "passive"))
      (node (ref "R60") (pin "2") (pinfunction "2_2") (pintype "passive"))
      (node (ref "R61") (pin "2") (pinfunction "2_2") (pintype "passive"))
      (node (ref "VD1") (pin "2") (pinfunction "A_2") (pintype "passive"))
      (node (ref "VD3") (pin "1") (pinfunction "C_1") (pintype "passive"))
      (node (ref "VT20") (pin "2") (pinfunction "D_2") (pintype "passive"))
    )
    (net (code "47") (name "Net-(VD1-C)") (class "Default")
      (node (ref "C38") (pin "2") (pinfunction "2_2") (pintype "passive"))
      (node (ref "C41") (pin "1") (pinfunction "1_1") (pintype "passive"))
      (node (ref "C42") (pin "1") (pinfunction "1_1") (pintype "passive"))
      (node (ref "C43") (pin "1") (pinfunction "1_1") (pintype "passive"))
      (node (ref "C44") (pin "1") (pinfunction "1_1") (pintype "passive"))
      (node (ref "C45") (pin "1") (pinfunction "1_1") (pintype "passive"))
      (node (ref "C46") (pin "1") (pinfunction "1_1") (pintype "passive"))
      (node (ref "C47") (pin "1") (pinfunction "1_1") (pintype "passive"))
      (node (ref "C48") (pin "1") (pinfunction "1_1") (pintype "passive"))
      (node (ref "L12") (pin "2") (pinfunction "2_2") (pintype "passive"))
      (node (ref "R27") (pin "1") (pinfunction "1_1") (pintype "passive"))
      (node (ref "R58") (pin "2") (pinfunction "2_2") (pintype "passive"))
      (node (ref "VD1") (pin "1") (pinfunction "C_1") (pintype "passive"))
      (node (ref "VT11") (pin "3") (pinfunction "E_3") (pintype "passive"))
      (node (ref "VT13") (pin "2") (pinfunction "C_2") (pintype "passive"))
      (node (ref "VT15") (pin "2") (pinfunction "C_2") (pintype "passive"))
      (node (ref "VT16") (pin "2") (pinfunction "C_2") (pintype "passive"))
      (node (ref "VT17") (pin "2") (pinfunction "C_2") (pintype "passive"))
    )
    (net (code "48") (name "Net-(VT11-B)") (class "Default")
      (node (ref "R27") (pin "2") (pinfunction "2_2") (pintype "passive"))
      (node (ref "VT11") (pin "1") (pinfunction "B_1") (pintype "passive"))
      (node (ref "VT12") (pin "3") (pinfunction "E_3") (pintype "passive"))
    )
    (net (code "49") (name "Net-(VT11-C)") (class "Default")
      (node (ref "R24") (pin "1") (pinfunction "1_1") (pintype "passive"))
      (node (ref "VT11") (pin "2") (pinfunction "C_2") (pintype "passive"))
      (node (ref "VT12") (pin "1") (pinfunction "B_1") (pintype "passive"))
    )
    (net (code "50") (name "Net-(VT12-C)") (class "Default")
      (node (ref "VT12") (pin "2") (pinfunction "C_2") (pintype "passive"))
      (node (ref "VT13") (pin "1") (pinfunction "B_1") (pintype "passive"))
      (node (ref "VT14") (pin "2") (pinfunction "C_2") (pintype "passive"))
    )
    (net (code "51") (name "Net-(VT13-E)") (class "Default")
      (node (ref "C56") (pin "1") (pinfunction "1_1") (pintype "passive"))
      (node (ref "VT13") (pin "3") (pinfunction "E_3") (pintype "passive"))
      (node (ref "VT15") (pin "1") (pinfunction "B_1") (pintype "passive"))
      (node (ref "VT16") (pin "1") (pinfunction "B_1") (pintype "passive"))
      (node (ref "VT17") (pin "1") (pinfunction "B_1") (pintype "passive"))
    )
    (net (code "52") (name "Net-(VT14-B)") (class "Default")
      (node (ref "C57") (pin "1") (pinfunction "1_1") (pintype "passive"))
      (node (ref "R33") (pin "1") (pinfunction "1_1") (pintype "passive"))
      (node (ref "VD2") (pin "1") (pinfunction "1_1") (pintype "passive"))
      (node (ref "VT14") (pin "1") (pinfunction "B_1") (pintype "passive"))
    )
    (net (code "53") (name "Net-(VT14-E)") (class "Default")
      (node (ref "R28") (pin "1") (pinfunction "1_1") (pintype "passive"))
      (node (ref "R29") (pin "1") (pinfunction "1_1") (pintype "passive"))
      (node (ref "VT14") (pin "3") (pinfunction "E_3") (pintype "passive"))
    )
    (net (code "54") (name "Net-(VT15-E)") (class "Default")
      (node (ref "R32") (pin "1") (pinfunction "1_1") (pintype "passive"))
      (node (ref "R61") (pin "1") (pinfunction "1_1") (pintype "passive"))
      (node (ref "VT15") (pin "3") (pinfunction "E_3") (pintype "passive"))
    )
    (net (code "55") (name "Net-(VT16-E)") (class "Default")
      (node (ref "R31") (pin "1") (pinfunction "1_1") (pintype "passive"))
      (node (ref "R60") (pin "1") (pinfunction "1_1") (pintype "passive"))
      (node (ref "VT16") (pin "3") (pinfunction "E_3") (pintype "passive"))
    )
    (net (code "56") (name "Net-(VT17-E)") (class "Default")
      (node (ref "R30") (pin "1") (pinfunction "1_1") (pintype "passive"))
      (node (ref "R59") (pin "1") (pinfunction "1_1") (pintype "passive"))
      (node (ref "VT17") (pin "3") (pinfunction "E_3") (pintype "passive"))
    )
    (net (code "57") (name "Net-(VT18-B)") (class "Default")
      (node (ref "R44") (pin "2") (pinfunction "2_2") (pintype "passive"))
      (node (ref "VT18") (pin "1") (pinfunction "B_1") (pintype "passive"))
      (node (ref "VT19") (pin "1") (pinfunction "B_1") (pintype "passive"))
    )
    (net (code "58") (name "Net-(VT18-E)") (class "Default")
      (node (ref "R49") (pin "2") (pinfunction "2_2") (pintype "passive"))
      (node (ref "VT18") (pin "3") (pinfunction "E_3") (pintype "passive"))
      (node (ref "VT19") (pin "3") (pinfunction "E_3") (pintype "passive"))
    )
    (net (code "59") (name "Net-(VT20-G)") (class "Default")
      (node (ref "R49") (pin "1") (pinfunction "1_1") (pintype "passive"))
      (node (ref "VT20") (pin "1") (pinfunction "G_1") (pintype "passive"))
    )
    (net (code "60") (name "Net-(VT20-S)") (class "Default")
      (node (ref "R50") (pin "2") (pinfunction "2_2") (pintype "passive"))
      (node (ref "R51") (pin "2") (pinfunction "2_2") (pintype "passive"))
      (node (ref "VT20") (pin "3") (pinfunction "S_3") (pintype "passive"))
    )
    (net (code "61") (name "Net-(VT21-B)") (class "Default")
      (node (ref "R56") (pin "2") (pinfunction "2_2") (pintype "passive"))
      (node (ref "R57") (pin "1") (pinfunction "1_1") (pintype "passive"))
      (node (ref "VT21") (pin "1") (pinfunction "B_1") (pintype "passive"))
    )
    (net (code "62") (name "VCC_5V0P") (class "Default")
      (node (ref "C65") (pin "2") (pinfunction "2_2") (pintype "passive"))
      (node (ref "C66") (pin "2") (pinfunction "2_2") (pintype "passive"))
      (node (ref "DA7") (pin "8") (pinfunction "VCC_8") (pintype "power_in"))
      (node (ref "DA8") (pin "8") (pinfunction "VCC_8") (pintype "power_in"))
      (node (ref "L11") (pin "2") (pinfunction "2_2") (pintype "passive"))
      (node (ref "R45") (pin "1") (pinfunction "1_1") (pintype "passive"))
      (node (ref "R46") (pin "1") (pinfunction "1_1") (pintype "passive"))
      (node (ref "R47") (pin "1") (pinfunction "1_1") (pintype "passive"))
      (node (ref "R48") (pin "1") (pinfunction "1_1") (pintype "passive"))
    )
    (net (code "63") (name "VCC_10V0N") (class "Default")
      (node (ref "L10") (pin "2") (pinfunction "2_2") (pintype "passive"))
      (node (ref "L8") (pin "2") (pinfunction "2_2") (pintype "passive"))
    )
    (net (code "64") (name "VCC_10V0P") (class "Default")
      (node (ref "L7") (pin "2") (pinfunction "2_2") (pintype "passive"))
      (node (ref "L9") (pin "2") (pinfunction "2_2") (pintype "passive"))
    )
    (net (code "65") (name "VCC_12V0") (class "Default")
      (node (ref "C67") (pin "1") (pinfunction "1_1") (pintype "passive"))
      (node (ref "VT18") (pin "2") (pinfunction "C_2") (pintype "passive"))
    )
    (net (code "66") (name "unconnected-(XP1-Pad4)") (class "Default")
      (node (ref "XP1") (pin "4") (pinfunction "4_4") (pintype "passive+no_connect"))
    )
    (net (code "67") (name "unconnected-(XP1-Pad6)") (class "Default")
      (node (ref "XP1") (pin "6") (pinfunction "6_6") (pintype "passive+no_connect"))
    )
  )
)
